# sensor_board.net
KiCad netlist of a schematic drawn in EAGLE
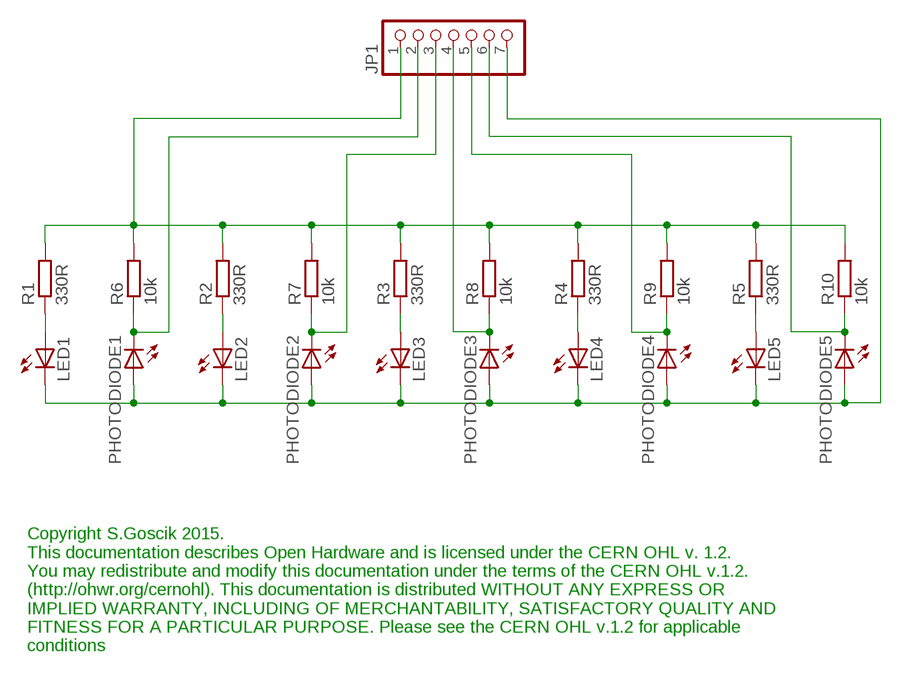
[diagram p0: schematic, sheet 1]

(export (version "E")
  (design (tool "Eeschema 10.0.6"))
  (components
    (comp (ref "JP1")
      (value "PINHD-1X7")
      (footprint "eagle-import:1X07")
      (libsource (lib "eagle-import") (part "PINHD-1X7"))
    )
    (comp (ref "LED1")
      (value "LED3MM")
      (footprint "eagle-import:LED3MM")
      (libsource (lib "eagle-import") (part "LED3MM"))
    )
    (comp (ref "LED2")
      (value "LED3MM")
      (footprint "eagle-import:LED3MM")
      (libsource (lib "eagle-import") (part "LED3MM"))
    )
    (comp (ref "LED3")
      (value "LED3MM")
      (footprint "eagle-import:LED3MM")
      (libsource (lib "eagle-import") (part "LED3MM"))
    )
    (comp (ref "LED4")
      (value "LED3MM")
      (footprint "eagle-import:LED3MM")
      (libsource (lib "eagle-import") (part "LED3MM"))
    )
    (comp (ref "LED5")
      (value "LED3MM")
      (footprint "eagle-import:LED3MM")
      (libsource (lib "eagle-import") (part "LED3MM"))
    )
    (comp (ref "PHOTODIODE1")
      (value "LED3MM")
      (footprint "eagle-import:LED3MM")
      (libsource (lib "eagle-import") (part "LED3MM"))
    )
    (comp (ref "PHOTODIODE2")
      (value "LED3MM")
      (footprint "eagle-import:LED3MM")
      (libsource (lib "eagle-import") (part "LED3MM"))
    )
    (comp (ref "PHOTODIODE3")
      (value "LED3MM")
      (footprint "eagle-import:LED3MM")
      (libsource (lib "eagle-import") (part "LED3MM"))
    )
    (comp (ref "PHOTODIODE4")
      (value "LED3MM")
      (footprint "eagle-import:LED3MM")
      (libsource (lib "eagle-import") (part "LED3MM"))
    )
    (comp (ref "PHOTODIODE5")
      (value "LED3MM")
      (footprint "eagle-import:LED3MM")
      (libsource (lib "eagle-import") (part "LED3MM"))
    )
    (comp (ref "R1")
      (value "330R")
      (footprint "eagle-import:0207_10")
      (libsource (lib "eagle-import") (part "R-EU_0207/10"))
    )
    (comp (ref "R2")
      (value "330R")
      (footprint "eagle-import:0207_10")
      (libsource (lib "eagle-import") (part "R-EU_0207/10"))
    )
    (comp (ref "R3")
      (value "330R")
      (footprint "eagle-import:0207_10")
      (libsource (lib "eagle-import") (part "R-EU_0207/10"))
    )
    (comp (ref "R4")
      (value "330R")
      (footprint "eagle-import:0207_10")
      (libsource (lib "eagle-import") (part "R-EU_0207/10"))
    )
    (comp (ref "R5")
      (value "330R")
      (footprint "eagle-import:0207_10")
      (libsource (lib "eagle-import") (part "R-EU_0207/10"))
    )
    (comp (ref "R6")
      (value "10k")
      (footprint "eagle-import:0207_10")
      (libsource (lib "eagle-import") (part "R-EU_0207/10"))
    )
    (comp (ref "R7")
      (value "10k")
      (footprint "eagle-import:0207_10")
      (libsource (lib "eagle-import") (part "R-EU_0207/10"))
    )
    (comp (ref "R8")
      (value "10k")
      (footprint "eagle-import:0207_10")
      (libsource (lib "eagle-import") (part "R-EU_0207/10"))
    )
    (comp (ref "R9")
      (value "10k")
      (footprint "eagle-import:0207_10")
      (libsource (lib "eagle-import") (part "R-EU_0207/10"))
    )
    (comp (ref "R10")
      (value "10k")
      (footprint "eagle-import:0207_10")
      (libsource (lib "eagle-import") (part "R-EU_0207/10"))
    )
  )
  (nets
    (net (code "1") (name "Net-(JP1-Pad1)") (class "Default")
      (node (ref "JP1") (pin "1") (pinfunction "1_1") (pintype "passive"))
      (node (ref "R1") (pin "2") (pinfunction "2_2") (pintype "passive"))
      (node (ref "R10") (pin "2") (pinfunction "2_2") (pintype "passive"))
      (node (ref "R2") (pin "2") (pinfunction "2_2") (pintype "passive"))
      (node (ref "R3") (pin "2") (pinfunction "2_2") (pintype "passive"))
      (node (ref "R4") (pin "2") (pinfunction "2_2") (pintype "passive"))
      (node (ref "R5") (pin "2") (pinfunction "2_2") (pintype "passive"))
      (node (ref "R6") (pin "2") (pinfunction "2_2") (pintype "passive"))
      (node (ref "R7") (pin "2") (pinfunction "2_2") (pintype "passive"))
      (node (ref "R8") (pin "2") (pinfunction "2_2") (pintype "passive"))
      (node (ref "R9") (pin "2") (pinfunction "2_2") (pintype "passive"))
    )
    (net (code "2") (name "Net-(LED1-C)") (class "Default")
      (node (ref "JP1") (pin "7") (pinfunction "7_7") (pintype "passive"))
      (node (ref "LED1") (pin "K") (pinfunction "C_K") (pintype "passive"))
      (node (ref "LED2") (pin "K") (pinfunction "C_K") (pintype "passive"))
      (node (ref "LED3") (pin "K") (pinfunction "C_K") (pintype "passive"))
      (node (ref "LED4") (pin "K") (pinfunction "C_K") (pintype "passive"))
      (node (ref "LED5") (pin "K") (pinfunction "C_K") (pintype "passive"))
      (node (ref "PHOTODIODE1") (pin "A") (pinfunction "A_A") (pintype "passive"))
      (node (ref "PHOTODIODE2") (pin "A") (pinfunction "A_A") (pintype "passive"))
      (node (ref "PHOTODIODE3") (pin "A") (pinfunction "A_A") (pintype "passive"))
      (node (ref "PHOTODIODE4") (pin "A") (pinfunction "A_A") (pintype "passive"))
      (node (ref "PHOTODIODE5") (pin "A") (pinfunction "A_A") (pintype "passive"))
    )
    (net (code "3") (name "Net-(LED1-PadA)") (class "Default")
      (node (ref "LED1") (pin "A") (pinfunction "A_A") (pintype "passive"))
      (node (ref "R1") (pin "1") (pinfunction "1_1") (pintype "passive"))
    )
    (net (code "4") (name "Net-(LED2-PadA)") (class "Default")
      (node (ref "LED2") (pin "A") (pinfunction "A_A") (pintype "passive"))
      (node (ref "R2") (pin "1") (pinfunction "1_1") (pintype "passive"))
    )
    (net (code "5") (name "Net-(LED3-PadA)") (class "Default")
      (node (ref "LED3") (pin "A") (pinfunction "A_A") (pintype "passive"))
      (node (ref "R3") (pin "1") (pinfunction "1_1") (pintype "passive"))
    )
    (net (code "6") (name "Net-(LED4-PadA)") (class "Default")
      (node (ref "LED4") (pin "A") (pinfunction "A_A") (pintype "passive"))
      (node (ref "R4") (pin "1") (pinfunction "1_1") (pintype "passive"))
    )
    (net (code "7") (name "Net-(LED5-PadA)") (class "Default")
      (node (ref "LED5") (pin "A") (pinfunction "A_A") (pintype "passive"))
      (node (ref "R5") (pin "1") (pinfunction "1_1") (pintype "passive"))
    )
    (net (code "8") (name "Net-(PHOTODIODE1-C)") (class "Default")
      (node (ref "JP1") (pin "2") (pinfunction "2_2") (pintype "passive"))
      (node (ref "PHOTODIODE1") (pin "K") (pinfunction "C_K") (pintype "passive"))
      (node (ref "R6") (pin "1") (pinfunction "1_1") (pintype "passive"))
    )
    (net (code "9") (name "Net-(PHOTODIODE2-C)") (class "Default")
      (node (ref "JP1") (pin "3") (pinfunction "3_3") (pintype "passive"))
      (node (ref "PHOTODIODE2") (pin "K") (pinfunction "C_K") (pintype "passive"))
      (node (ref "R7") (pin "1") (pinfunction "1_1") (pintype "passive"))
    )
    (net (code "10") (name "Net-(PHOTODIODE3-C)") (class "Default")
      (node (ref "JP1") (pin "4") (pinfunction "4_4") (pintype "passive"))
      (node (ref "PHOTODIODE3") (pin "K") (pinfunction "C_K") (pintype "passive"))
      (node (ref "R8") (pin "1") (pinfunction "1_1") (pintype "passive"))
    )
    (net (code "11") (name "Net-(PHOTODIODE4-C)") (class "Default")
      (node (ref "JP1") (pin "5") (pinfunction "5_5") (pintype "passive"))
      (node (ref "PHOTODIODE4") (pin "K") (pinfunction "C_K") (pintype "passive"))
      (node (ref "R9") (pin "1") (pinfunction "1_1") (pintype "passive"))
    )
    (net (code "12") (name "Net-(PHOTODIODE5-C)") (class "Default")
      (node (ref "JP1") (pin "6") (pinfunction "6_6") (pintype "passive"))
      (node (ref "PHOTODIODE5") (pin "K") (pinfunction "C_K") (pintype "passive"))
      (node (ref "R10") (pin "1") (pinfunction "1_1") (pintype "passive"))
    )
  )
)
